# Triggers.net
KiCad netlist of a schematic drawn in Altium Designer
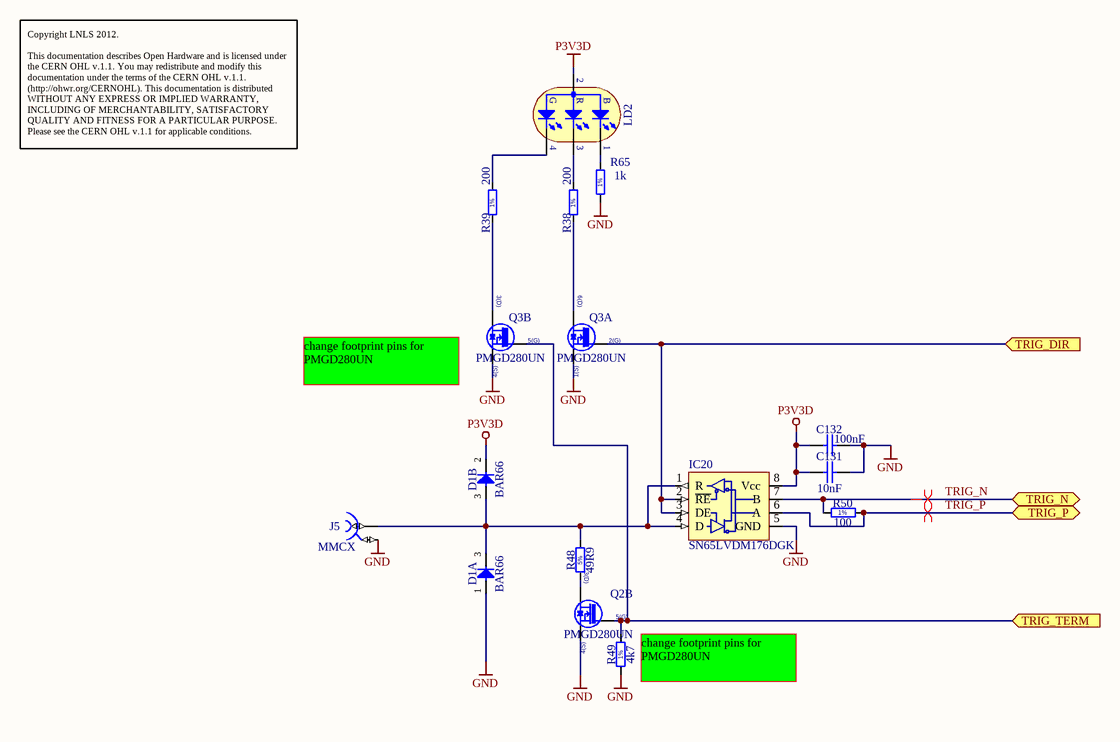
[diagram p0: Triggers.SchDoc]

(export (version "E")
  (design (tool "Eeschema 10.0.6"))
  (components
    (comp (ref "C131")
      (value "10nF")
      (footprint "CAPC0603X33N")
      (description "Non-polarised capacitor")
      (fields
        (field (name "PART NUMBER") "CC0201_10NF_10V_10%_X7R")
        (field (name "VOLTAGE") "10V")
        (field (name "AUTHOR") "LNLS DIG GBMB")
      )
      (libsource (lib "Capacitors") (part "Capacitor - non polarized"))
    )
    (comp (ref "C132")
      (value "100nF")
      (footprint "CAPC0603X33N")
      (description "Non-polarised capacitor")
      (fields
        (field (name "PART NUMBER") "CC0201_100NF_6.3V_10%_X5R")
        (field (name "VOLTAGE") "6.3V")
        (field (name "AUTHOR") "CERN DEM JLC")
      )
      (libsource (lib "Capacitors") (part "Capacitor - non polarized"))
    )
    (comp (ref "D1")
      (value "BAR66")
      (footprint "SOT95P240X110-3N")
      (description "Serial Diode")
      (fields
        (field (name "VOLTAGE") "150V")
        (field (name "POWER") "250mA")
        (field (name "AUTHOR") "CERN DEM JLC")
      )
      (libsource (lib "ICs And Semiconductors") (part "Diode x2 A1C3_A3C2"))
    )
    (comp (ref "IC20")
      (value "SN65LVDM176DGK")
      (footprint "SOP65P490X110-8N")
      (description "Differential Bus Transceiver")
      (fields (field (name "MANUFACTURER") "TEXAS INSTRUMENTS") (field (name "AUTHOR") "LNLS DIG GBMB"))
      (libsource (lib "ICs And Semiconductors_LNLS") (part "5176"))
    )
    (comp (ref "J5")
      (value "MMCX")
      (footprint "HUBER-SUHNER_85_MMCX-50-0-1/111_OH")
      (fields
        (field (name "PART NUMBER") "HUBER-SUHNER_85_MMCX-50-0-1/111_OH")
        (field (name "MANUFACTURER") "HUBER+SUHNER")
        (field (name "MANUFACTURER PART NUMBER") "85_MMCX-50-0-1/111_OH")
        (field (name "AUTHOR") "CERN DEM JLC")
      )
      (libsource (lib "Connectors") (part "Coax_1Female_1Shield"))
    )
    (comp (ref "LD2")
      (value "~")
      (footprint "LED_AVAGO_HSMF-C113")
      (description "Tricolor LEDs 1 Cathode Blue, 2 Common Anode, 3 Cathode Red, 4 Cathode Green")
      (fields
        (field (name "PART NUMBER") "LED_AVAGO_HSMF-C113")
        (field (name "MANUFACTURER") "AVAGO TECHNOLOGIES")
        (field (name "AUTHOR") "CERN DEM JLC")
      )
      (libsource (lib "ICs And Semiconductors") (part "LED Blue-Red-Green 1CB_2AC_3CR_4CG"))
    )
    (comp (ref "Q2")
      (value "PMGD280UN")
      (footprint "SOT65P210X110-6N")
      (description "Dual N-Channel micro TrenchMOS™ Ultra Low Level FET")
      (fields (field (name "MANUFACTURER") "NXP SEMICONDUCTORS") (field (name "AUTHOR") "CERN DEM JLC"))
      (libsource (lib "ICs And Semiconductors") (part "PMGD280UN"))
    )
    (comp (ref "Q3")
      (value "PMGD280UN")
      (footprint "SOT65P210X110-6N")
      (description "Dual N-Channel micro TrenchMOS™ Ultra Low Level FET")
      (fields (field (name "MANUFACTURER") "NXP SEMICONDUCTORS") (field (name "AUTHOR") "CERN DEM JLC"))
      (libsource (lib "") (part "PMGD280UN_1"))
    )
    (comp (ref "R38")
      (value "200")
      (footprint "RESC1005X40N")
      (description "Resistor - 1%")
      (fields
        (field (name "PART NUMBER") "R0402_200R_1%_0.0625W_100PPM")
        (field (name "POWER") "0.0625W")
        (field (name "AUTHOR") "CERN DEM JLC")
      )
      (libsource (lib "Resistors") (part "Resistor - 1%"))
    )
    (comp (ref "R39")
      (value "200")
      (footprint "RESC1005X40N")
      (description "Resistor - 1%")
      (fields
        (field (name "PART NUMBER") "R0402_200R_1%_0.0625W_100PPM")
        (field (name "POWER") "0.0625W")
        (field (name "AUTHOR") "CERN DEM JLC")
      )
      (libsource (lib "Resistors") (part "Resistor - 1%"))
    )
    (comp (ref "R48")
      (value "49R9")
      (footprint "RESC3225X70N")
      (description "Resistor - 5%")
      (fields
        (field (name "PART NUMBER") "R1210_49R9_1%_0.33W_100PPM")
        (field (name "POWER") "0.33W")
        (field (name "AUTHOR") "CERN DEM JLC")
      )
      (libsource (lib "Resistors") (part "Resistor - 5%"))
    )
    (comp (ref "R49")
      (value "4k7")
      (footprint "RESC1005X40N")
      (description "Resistor - 1%")
      (fields
        (field (name "PART NUMBER") "R0402_4K7_1%_0.0625W_100PPM")
        (field (name "POWER") "0.0625W")
        (field (name "AUTHOR") "CERN DEM JLC")
      )
      (libsource (lib "Resistors") (part "Resistor - 1%"))
    )
    (comp (ref "R50")
      (value "100")
      (footprint "RESC1005X40N")
      (description "Resistor - 1%")
      (fields
        (field (name "PART NUMBER") "R0402_100R_1%_0.0625W_100PPM")
        (field (name "POWER") "0.0625W")
        (field (name "AUTHOR") "CERN DEM JLC")
      )
      (libsource (lib "Resistors") (part "Resistor - 1%"))
    )
    (comp (ref "R65")
      (value "1k")
      (footprint "RESC1005X40N")
      (description "Resistor - 1%")
      (fields
        (field (name "PART NUMBER") "R0402_1K_1%_0.0625W_100PPM")
        (field (name "POWER") "0.0625W")
        (field (name "AUTHOR") "CERN DEM JLC")
      )
      (libsource (lib "Resistors") (part "Resistor - 1%"))
    )
  )
  (nets
    (net (code "1") (name "/TRIG_DIR") (class "Default")
      (node (ref "IC20") (pin "2") (pinfunction "~{RE}_2") (pintype "input"))
      (node (ref "IC20") (pin "3") (pinfunction "DE_3") (pintype "input"))
      (node (ref "Q3") (pin "2") (pinfunction "G_2") (pintype "passive"))
    )
    (net (code "2") (name "/TRIG_N") (class "Default")
      (node (ref "IC20") (pin "7") (pinfunction "B_7") (pintype "bidirectional"))
      (node (ref "R50") (pin "1") (pinfunction "1_1") (pintype "passive"))
    )
    (net (code "3") (name "/TRIG_P") (class "Default")
      (node (ref "IC20") (pin "6") (pinfunction "A_6") (pintype "bidirectional"))
      (node (ref "R50") (pin "2") (pinfunction "2_2") (pintype "passive"))
    )
    (net (code "4") (name "/TRIG_TERM") (class "Default")
      (node (ref "Q2") (pin "5") (pinfunction "G_5") (pintype "passive"))
      (node (ref "Q3") (pin "5") (pinfunction "G_5") (pintype "passive"))
      (node (ref "R49") (pin "2") (pinfunction "2_2") (pintype "passive"))
    )
    (net (code "5") (name "GND") (class "Default")
      (node (ref "C131") (pin "2") (pinfunction "2_2") (pintype "passive"))
      (node (ref "C132") (pin "2") (pinfunction "2_2") (pintype "passive"))
      (node (ref "D1") (pin "1") (pinfunction "A_1") (pintype "passive"))
      (node (ref "IC20") (pin "5") (pinfunction "GND_5") (pintype "power_in"))
      (node (ref "J5") (pin "2") (pinfunction "2_2") (pintype "bidirectional"))
      (node (ref "Q2") (pin "4") (pinfunction "S_4") (pintype "passive"))
      (node (ref "Q3") (pin "1") (pinfunction "S_1") (pintype "passive"))
      (node (ref "Q3") (pin "4") (pinfunction "S_4") (pintype "passive"))
      (node (ref "R49") (pin "1") (pinfunction "1_1") (pintype "passive"))
      (node (ref "R65") (pin "1") (pinfunction "1_1") (pintype "passive"))
    )
    (net (code "6") (name "Net-(D1A-COMAC)") (class "Default")
      (node (ref "D1") (pin "3") (pinfunction "COMAC_3") (pintype "passive"))
      (node (ref "IC20") (pin "1") (pinfunction "R_1") (pintype "output"))
      (node (ref "IC20") (pin "4") (pinfunction "D_4") (pintype "input"))
      (node (ref "J5") (pin "1") (pinfunction "1_1") (pintype "bidirectional"))
      (node (ref "R48") (pin "2") (pinfunction "2_2") (pintype "passive"))
    )
    (net (code "7") (name "Net-(LD2-CB)") (class "Default")
      (node (ref "LD2") (pin "1") (pinfunction "CB_1") (pintype "passive"))
      (node (ref "R65") (pin "2") (pinfunction "2_2") (pintype "passive"))
    )
    (net (code "8") (name "Net-(LD2-CG)") (class "Default")
      (node (ref "LD2") (pin "4") (pinfunction "CG_4") (pintype "passive"))
      (node (ref "R39") (pin "2") (pinfunction "2_2") (pintype "passive"))
    )
    (net (code "9") (name "Net-(LD2-CR)") (class "Default")
      (node (ref "LD2") (pin "3") (pinfunction "CR_3") (pintype "passive"))
      (node (ref "R38") (pin "2") (pinfunction "2_2") (pintype "passive"))
    )
    (net (code "10") (name "Net-(Q2B-D)") (class "Default")
      (node (ref "Q2") (pin "3") (pinfunction "D_3") (pintype "passive"))
      (node (ref "R48") (pin "1") (pinfunction "1_1") (pintype "passive"))
    )
    (net (code "11") (name "Net-(Q3A-D)") (class "Default")
      (node (ref "Q3") (pin "6") (pinfunction "D_6") (pintype "passive"))
      (node (ref "R38") (pin "1") (pinfunction "1_1") (pintype "passive"))
    )
    (net (code "12") (name "Net-(Q3B-D)") (class "Default")
      (node (ref "Q3") (pin "3") (pinfunction "D_3") (pintype "passive"))
      (node (ref "R39") (pin "1") (pinfunction "1_1") (pintype "passive"))
    )
    (net (code "13") (name "P3V3D") (class "Default")
      (node (ref "C131") (pin "1") (pinfunction "1_1") (pintype "passive"))
      (node (ref "C132") (pin "1") (pinfunction "1_1") (pintype "passive"))
      (node (ref "D1") (pin "2") (pinfunction "C_2") (pintype "passive"))
      (node (ref "IC20") (pin "8") (pinfunction "Vcc_8") (pintype "power_in"))
      (node (ref "LD2") (pin "2") (pinfunction "AC_2") (pintype "passive"))
    )
  )
)
